# lorasch.net
KiCad netlist of a schematic drawn in EAGLE
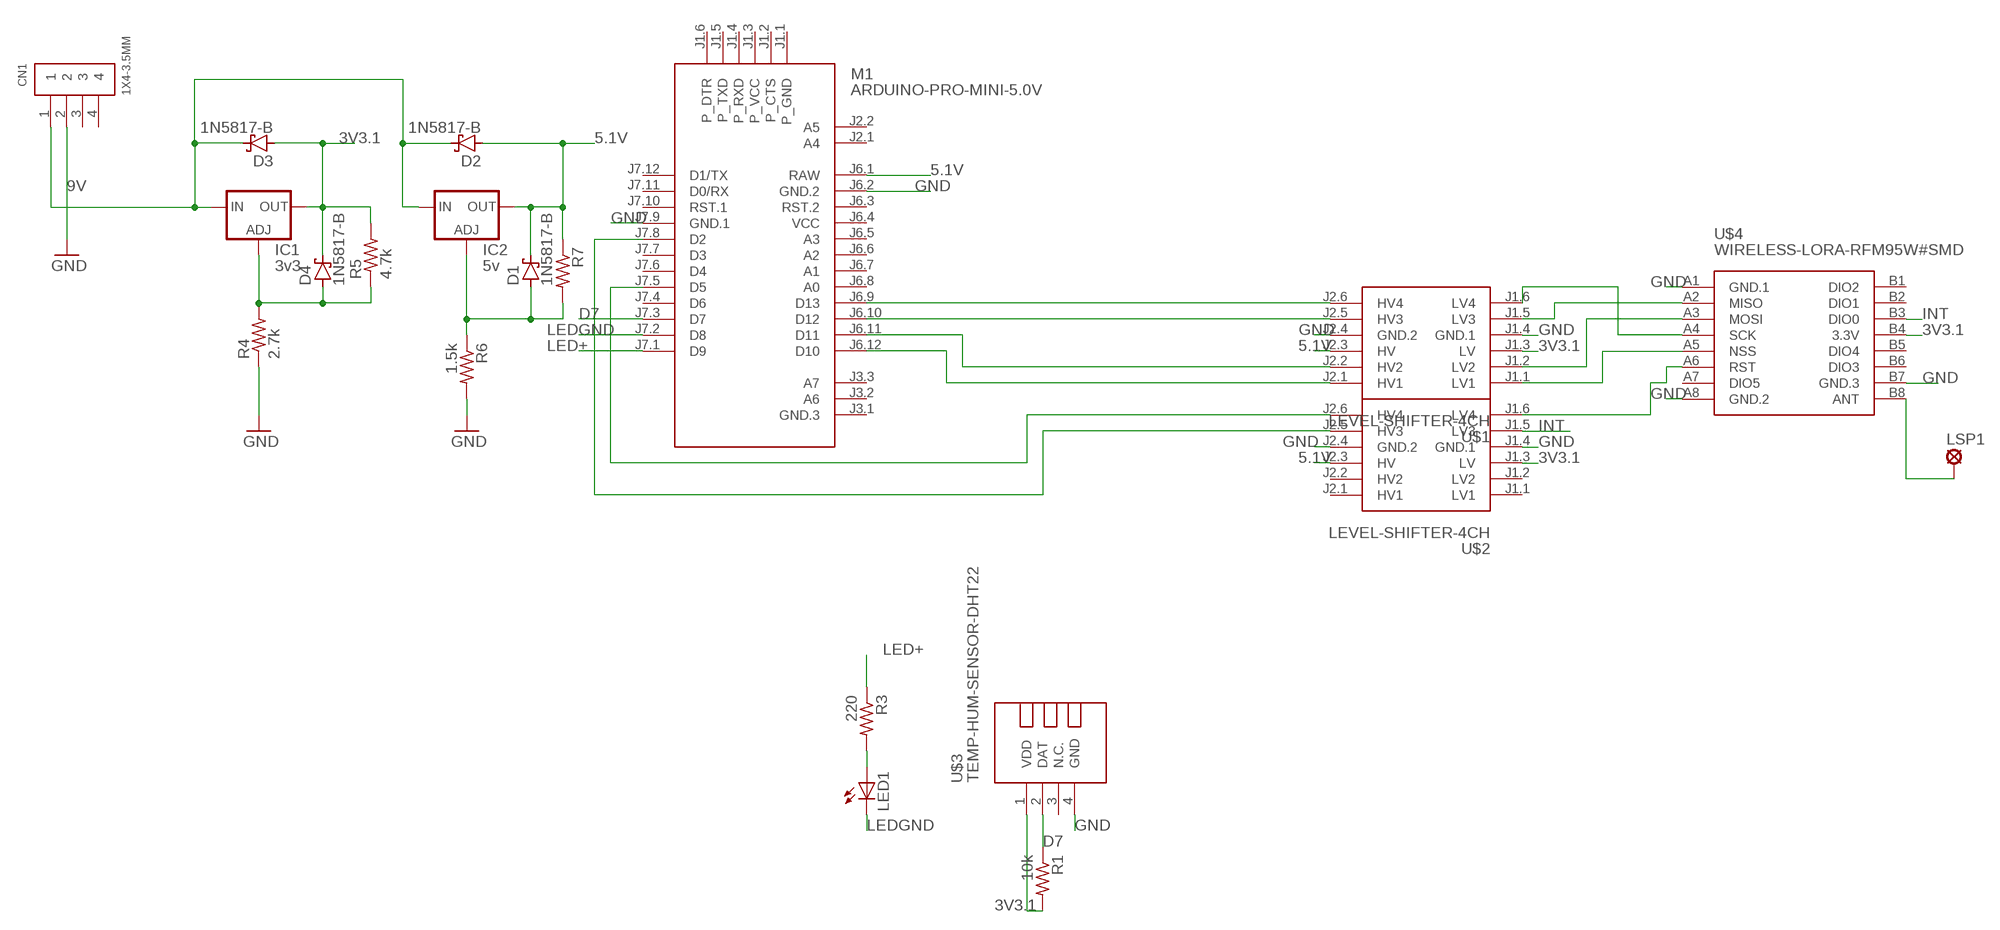
[diagram p0: schematic, sheet 1]

(export (version "E")
  (design (tool "Eeschema 10.0.6"))
  (components
    (comp (ref "CN1")
      (value "1X4-3.5MM")
      (footprint "eagle-import:1X04-3.5MM")
      (libsource (lib "eagle-import") (part "1X4-3.5MM"))
    )
    (comp (ref "D1")
      (value "1N5817-B")
      (footprint "eagle-import:DO41-7.6")
      (libsource (lib "eagle-import") (part "1N5817-B"))
    )
    (comp (ref "D2")
      (value "1N5817-B")
      (footprint "eagle-import:DO41-7.6")
      (libsource (lib "eagle-import") (part "1N5817-B"))
    )
    (comp (ref "D3")
      (value "1N5817-B")
      (footprint "eagle-import:DO41-7.6")
      (libsource (lib "eagle-import") (part "1N5817-B"))
    )
    (comp (ref "D4")
      (value "1N5817-B")
      (footprint "eagle-import:DO41-7.6")
      (libsource (lib "eagle-import") (part "1N5817-B"))
    )
    (comp (ref "IC1")
      (value "3v3")
      (footprint "eagle-import:317TL")
      (libsource (lib "eagle-import") (part "LM317TL"))
    )
    (comp (ref "IC2")
      (value "5v")
      (footprint "eagle-import:317TL")
      (libsource (lib "eagle-import") (part "LM317TL"))
    )
    (comp (ref "LED1")
      (value "LED5MM")
      (footprint "eagle-import:LED5MM")
      (libsource (lib "eagle-import") (part "LED5MM"))
    )
    (comp (ref "LSP1")
      (value "SE14")
      (footprint "eagle-import:SE14")
      (libsource (lib "eagle-import") (part "SE14"))
    )
    (comp (ref "M1")
      (value "ARDUINO-PRO-MINI-5.0V")
      (footprint "eagle-import:ARDUINO-PRO-MINI")
      (libsource (lib "eagle-import") (part "ARDUINO-PRO-MINI-5.0V"))
    )
    (comp (ref "R1")
      (value "10k")
      (footprint "eagle-import:0204_7")
      (libsource (lib "eagle-import") (part "R-US_0204/7"))
    )
    (comp (ref "R3")
      (value "220")
      (footprint "eagle-import:0204_7")
      (libsource (lib "eagle-import") (part "R-US_0204/7"))
    )
    (comp (ref "R4")
      (value "2.7k")
      (footprint "eagle-import:0204_7")
      (libsource (lib "eagle-import") (part "R-US_0204/7"))
    )
    (comp (ref "R5")
      (value "4.7k")
      (footprint "eagle-import:0204_7")
      (libsource (lib "eagle-import") (part "R-US_0204/7"))
    )
    (comp (ref "R6")
      (value "1.5k")
      (footprint "eagle-import:0204_7")
      (libsource (lib "eagle-import") (part "R-US_0204/7"))
    )
    (comp (ref "R7")
      (value "R-US_0204/7")
      (footprint "eagle-import:0204_7")
      (libsource (lib "eagle-import") (part "R-US_0204/7"))
    )
    (comp (ref "U$1")
      (value "LEVEL-SHIFTER-4CH")
      (footprint "eagle-import:LEVEL-SHIFTER-4CH")
      (libsource (lib "eagle-import") (part "LEVEL-SHIFTER-4CH"))
    )
    (comp (ref "U$2")
      (value "LEVEL-SHIFTER-4CH")
      (footprint "eagle-import:LEVEL-SHIFTER-4CH")
      (libsource (lib "eagle-import") (part "LEVEL-SHIFTER-4CH"))
    )
    (comp (ref "U$3")
      (value "TEMP-HUM-SENSOR-DHT22")
      (footprint "eagle-import:TEMP-HUM-SENSOR-DHT22")
      (libsource (lib "eagle-import") (part "TEMP-HUM-SENSOR-DHT22"))
    )
    (comp (ref "U$4")
      (value "WIRELESS-LORA-RFM95W#SMD")
      (footprint "eagle-import:WIRELESS-LORA-RFM95W#SMD")
      (libsource (lib "eagle-import") (part "WIRELESS-LORA-RFM95W#SMD"))
    )
  )
  (nets
    (net (code "1") (name "/3V3.1") (class "Default")
      (node (ref "D3") (pin "A") (pinfunction "A_A") (pintype "passive"))
      (node (ref "D4") (pin "C") (pinfunction "C_C") (pintype "passive"))
      (node (ref "IC1") (pin "2") (pinfunction "OUT_2") (pintype "passive"))
      (node (ref "R1") (pin "2") (pinfunction "2_2") (pintype "passive"))
      (node (ref "R5") (pin "2") (pinfunction "2_2") (pintype "passive"))
      (node (ref "U$1") (pin "J1.3") (pinfunction "LV_J1.3") (pintype "power_in"))
      (node (ref "U$2") (pin "J1.3") (pinfunction "LV_J1.3") (pintype "power_in"))
      (node (ref "U$3") (pin "1") (pinfunction "VDD_1") (pintype "power_in"))
      (node (ref "U$4") (pin "B4") (pinfunction "3.3V_B4") (pintype "power_in"))
    )
    (net (code "2") (name "/5.1V") (class "Default")
      (node (ref "D1") (pin "C") (pinfunction "C_C") (pintype "passive"))
      (node (ref "D2") (pin "A") (pinfunction "A_A") (pintype "passive"))
      (node (ref "IC2") (pin "2") (pinfunction "OUT_2") (pintype "passive"))
      (node (ref "M1") (pin "J6.1") (pinfunction "RAW_J6.1") (pintype "power_in"))
      (node (ref "R7") (pin "1") (pinfunction "1_1") (pintype "passive"))
      (node (ref "U$1") (pin "J2.3") (pinfunction "HV_J2.3") (pintype "power_in"))
      (node (ref "U$2") (pin "J2.3") (pinfunction "HV_J2.3") (pintype "power_in"))
    )
    (net (code "3") (name "/9V") (class "Default")
      (node (ref "CN1") (pin "1") (pinfunction "1_1") (pintype "bidirectional"))
      (node (ref "D2") (pin "C") (pinfunction "C_C") (pintype "passive"))
      (node (ref "D3") (pin "C") (pinfunction "C_C") (pintype "passive"))
      (node (ref "IC1") (pin "3") (pinfunction "IN_3") (pintype "input"))
      (node (ref "IC2") (pin "3") (pinfunction "IN_3") (pintype "input"))
    )
    (net (code "4") (name "/D7") (class "Default")
      (node (ref "M1") (pin "J7.3") (pinfunction "D7_J7.3") (pintype "bidirectional"))
      (node (ref "R1") (pin "1") (pinfunction "1_1") (pintype "passive"))
      (node (ref "U$3") (pin "2") (pinfunction "DAT_2") (pintype "bidirectional"))
    )
    (net (code "5") (name "/INT") (class "Default")
      (node (ref "U$2") (pin "J1.5") (pinfunction "LV3_J1.5") (pintype "bidirectional"))
      (node (ref "U$4") (pin "B3") (pinfunction "DIO0_B3") (pintype "bidirectional"))
    )
    (net (code "6") (name "/LED+") (class "Default")
      (node (ref "M1") (pin "J7.1") (pinfunction "D9_J7.1") (pintype "bidirectional"))
      (node (ref "R3") (pin "1") (pinfunction "1_1") (pintype "passive"))
    )
    (net (code "7") (name "/LEDGND") (class "Default")
      (node (ref "LED1") (pin "K") (pinfunction "C_K") (pintype "passive"))
      (node (ref "M1") (pin "J7.2") (pinfunction "D8_J7.2") (pintype "bidirectional"))
    )
    (net (code "8") (name "/VCC") (class "Default")
      (node (ref "M1") (pin "J6.4") (pinfunction "VCC_J6.4") (pintype "power_in"))
    )
    (net (code "9") (name "GND") (class "Default")
      (node (ref "CN1") (pin "2") (pinfunction "2_2") (pintype "bidirectional"))
      (node (ref "M1") (pin "J6.2") (pinfunction "GND.2_J6.2") (pintype "power_in"))
      (node (ref "M1") (pin "J7.9") (pinfunction "GND.1_J7.9") (pintype "power_in"))
      (node (ref "R4") (pin "1") (pinfunction "1_1") (pintype "passive"))
      (node (ref "R6") (pin "2") (pinfunction "2_2") (pintype "passive"))
      (node (ref "U$1") (pin "J1.4") (pinfunction "GND.1_J1.4") (pintype "power_in"))
      (node (ref "U$1") (pin "J2.4") (pinfunction "GND.2_J2.4") (pintype "power_in"))
      (node (ref "U$2") (pin "J1.4") (pinfunction "GND.1_J1.4") (pintype "power_in"))
      (node (ref "U$2") (pin "J2.4") (pinfunction "GND.2_J2.4") (pintype "power_in"))
      (node (ref "U$3") (pin "4") (pinfunction "GND_4") (pintype "power_in"))
      (node (ref "U$4") (pin "A1") (pinfunction "GND.1_A1") (pintype "power_in"))
      (node (ref "U$4") (pin "A8") (pinfunction "GND.2_A8") (pintype "power_in"))
      (node (ref "U$4") (pin "B7") (pinfunction "GND.3_B7") (pintype "power_in"))
    )
    (net (code "10") (name "Net-(IC1-ADJ)") (class "Default")
      (node (ref "D4") (pin "A") (pinfunction "A_A") (pintype "passive"))
      (node (ref "IC1") (pin "1") (pinfunction "ADJ_1") (pintype "input"))
      (node (ref "R4") (pin "2") (pinfunction "2_2") (pintype "passive"))
      (node (ref "R5") (pin "1") (pinfunction "1_1") (pintype "passive"))
    )
    (net (code "11") (name "Net-(IC2-ADJ)") (class "Default")
      (node (ref "D1") (pin "A") (pinfunction "A_A") (pintype "passive"))
      (node (ref "IC2") (pin "1") (pinfunction "ADJ_1") (pintype "input"))
      (node (ref "R6") (pin "1") (pinfunction "1_1") (pintype "passive"))
      (node (ref "R7") (pin "2") (pinfunction "2_2") (pintype "passive"))
    )
    (net (code "12") (name "Net-(LED1-PadA)") (class "Default")
      (node (ref "LED1") (pin "A") (pinfunction "A_A") (pintype "passive"))
      (node (ref "R3") (pin "2") (pinfunction "2_2") (pintype "passive"))
    )
    (net (code "13") (name "Net-(M1-D2)") (class "Default")
      (node (ref "M1") (pin "J7.8") (pinfunction "D2_J7.8") (pintype "bidirectional"))
      (node (ref "U$2") (pin "J2.5") (pinfunction "HV3_J2.5") (pintype "bidirectional"))
    )
    (net (code "14") (name "Net-(M1-D5)") (class "Default")
      (node (ref "M1") (pin "J7.5") (pinfunction "D5_J7.5") (pintype "bidirectional"))
      (node (ref "U$2") (pin "J2.6") (pinfunction "HV4_J2.6") (pintype "bidirectional"))
    )
    (net (code "15") (name "Net-(M1-D10)") (class "Default")
      (node (ref "M1") (pin "J6.12") (pinfunction "D10_J6.12") (pintype "bidirectional"))
      (node (ref "U$1") (pin "J2.1") (pinfunction "HV1_J2.1") (pintype "bidirectional"))
    )
    (net (code "16") (name "Net-(M1-D11)") (class "Default")
      (node (ref "M1") (pin "J6.11") (pinfunction "D11_J6.11") (pintype "bidirectional"))
      (node (ref "U$1") (pin "J2.2") (pinfunction "HV2_J2.2") (pintype "bidirectional"))
    )
    (net (code "17") (name "Net-(M1-D12)") (class "Default")
      (node (ref "M1") (pin "J6.10") (pinfunction "D12_J6.10") (pintype "bidirectional"))
      (node (ref "U$1") (pin "J2.5") (pinfunction "HV3_J2.5") (pintype "bidirectional"))
    )
    (net (code "18") (name "Net-(M1-D13)") (class "Default")
      (node (ref "M1") (pin "J6.9") (pinfunction "D13_J6.9") (pintype "bidirectional"))
      (node (ref "U$1") (pin "J2.6") (pinfunction "HV4_J2.6") (pintype "bidirectional"))
    )
    (net (code "19") (name "Net-(U$1-LV1)") (class "Default")
      (node (ref "U$1") (pin "J1.1") (pinfunction "LV1_J1.1") (pintype "bidirectional"))
      (node (ref "U$4") (pin "A5") (pinfunction "NSS_A5") (pintype "bidirectional"))
    )
    (net (code "20") (name "Net-(U$1-LV2)") (class "Default")
      (node (ref "U$1") (pin "J1.2") (pinfunction "LV2_J1.2") (pintype "bidirectional"))
      (node (ref "U$4") (pin "A3") (pinfunction "MOSI_A3") (pintype "bidirectional"))
    )
    (net (code "21") (name "Net-(U$1-LV3)") (class "Default")
      (node (ref "U$1") (pin "J1.5") (pinfunction "LV3_J1.5") (pintype "bidirectional"))
      (node (ref "U$4") (pin "A2") (pinfunction "MISO_A2") (pintype "bidirectional"))
    )
    (net (code "22") (name "Net-(U$1-LV4)") (class "Default")
      (node (ref "U$1") (pin "J1.6") (pinfunction "LV4_J1.6") (pintype "bidirectional"))
      (node (ref "U$4") (pin "A4") (pinfunction "SCK_A4") (pintype "bidirectional"))
    )
    (net (code "23") (name "Net-(U$2-LV4)") (class "Default")
      (node (ref "U$2") (pin "J1.6") (pinfunction "LV4_J1.6") (pintype "bidirectional"))
      (node (ref "U$4") (pin "A6") (pinfunction "RST_A6") (pintype "bidirectional"))
    )
    (net (code "24") (name "Net-(U$4-ANT)") (class "Default")
      (node (ref "LSP1") (pin "MP") (pinfunction "MP_MP") (pintype "passive"))
      (node (ref "U$4") (pin "B8") (pinfunction "ANT_B8") (pintype "passive"))
    )
    (net (code "25") (name "unconnected-(CN1-Pad3)") (class "Default")
      (node (ref "CN1") (pin "3") (pinfunction "3_3") (pintype "bidirectional"))
    )
    (net (code "26") (name "unconnected-(CN1-Pad4)") (class "Default")
      (node (ref "CN1") (pin "4") (pinfunction "4_4") (pintype "bidirectional"))
    )
    (net (code "27") (name "unconnected-(M1-A0-PadJ6.8)") (class "Default")
      (node (ref "M1") (pin "J6.8") (pinfunction "A0_J6.8") (pintype "bidirectional"))
    )
    (net (code "28") (name "unconnected-(M1-A1-PadJ6.7)") (class "Default")
      (node (ref "M1") (pin "J6.7") (pinfunction "A1_J6.7") (pintype "bidirectional"))
    )
    (net (code "29") (name "unconnected-(M1-A2-PadJ6.6)") (class "Default")
      (node (ref "M1") (pin "J6.6") (pinfunction "A2_J6.6") (pintype "bidirectional"))
    )
    (net (code "30") (name "unconnected-(M1-A3-PadJ6.5)") (class "Default")
      (node (ref "M1") (pin "J6.5") (pinfunction "A3_J6.5") (pintype "bidirectional"))
    )
    (net (code "31") (name "unconnected-(M1-A4-PadJ2.1)") (class "Default")
      (node (ref "M1") (pin "J2.1") (pinfunction "A4_J2.1") (pintype "bidirectional"))
    )
    (net (code "32") (name "unconnected-(M1-A5-PadJ2.2)") (class "Default")
      (node (ref "M1") (pin "J2.2") (pinfunction "A5_J2.2") (pintype "bidirectional"))
    )
    (net (code "33") (name "unconnected-(M1-A6-PadJ3.2)") (class "Default")
      (node (ref "M1") (pin "J3.2") (pinfunction "A6_J3.2") (pintype "bidirectional"))
    )
    (net (code "34") (name "unconnected-(M1-A7-PadJ3.3)") (class "Default")
      (node (ref "M1") (pin "J3.3") (pinfunction "A7_J3.3") (pintype "bidirectional"))
    )
    (net (code "35") (name "unconnected-(M1-D0{slash}RX-PadJ7.11)") (class "Default")
      (node (ref "M1") (pin "J7.11") (pinfunction "D0/RX_J7.11") (pintype "bidirectional"))
    )
    (net (code "36") (name "unconnected-(M1-D1{slash}TX-PadJ7.12)") (class "Default")
      (node (ref "M1") (pin "J7.12") (pinfunction "D1/TX_J7.12") (pintype "bidirectional"))
    )
    (net (code "37") (name "unconnected-(M1-D3-PadJ7.7)") (class "Default")
      (node (ref "M1") (pin "J7.7") (pinfunction "D3_J7.7") (pintype "bidirectional"))
    )
    (net (code "38") (name "unconnected-(M1-D4-PadJ7.6)") (class "Default")
      (node (ref "M1") (pin "J7.6") (pinfunction "D4_J7.6") (pintype "bidirectional"))
    )
    (net (code "39") (name "unconnected-(M1-D6-PadJ7.4)") (class "Default")
      (node (ref "M1") (pin "J7.4") (pinfunction "D6_J7.4") (pintype "bidirectional"))
    )
    (net (code "40") (name "unconnected-(M1-GND.3-PadJ3.1)") (class "Default")
      (node (ref "M1") (pin "J3.1") (pinfunction "GND.3_J3.1") (pintype "bidirectional"))
    )
    (net (code "41") (name "unconnected-(M1-P_CTS-PadJ1.2)") (class "Default")
      (node (ref "M1") (pin "J1.2") (pinfunction "P_CTS_J1.2") (pintype "bidirectional"))
    )
    (net (code "42") (name "unconnected-(M1-P_DTR-PadJ1.6)") (class "Default")
      (node (ref "M1") (pin "J1.6") (pinfunction "P_DTR_J1.6") (pintype "bidirectional"))
    )
    (net (code "43") (name "unconnected-(M1-P_GND-PadJ1.1)") (class "Default")
      (node (ref "M1") (pin "J1.1") (pinfunction "P_GND_J1.1") (pintype "bidirectional"))
    )
    (net (code "44") (name "unconnected-(M1-P_RXD-PadJ1.4)") (class "Default")
      (node (ref "M1") (pin "J1.4") (pinfunction "P_RXD_J1.4") (pintype "bidirectional"))
    )
    (net (code "45") (name "unconnected-(M1-P_TXD-PadJ1.5)") (class "Default")
      (node (ref "M1") (pin "J1.5") (pinfunction "P_TXD_J1.5") (pintype "bidirectional"))
    )
    (net (code "46") (name "unconnected-(M1-P_VCC-PadJ1.3)") (class "Default")
      (node (ref "M1") (pin "J1.3") (pinfunction "P_VCC_J1.3") (pintype "bidirectional"))
    )
    (net (code "47") (name "unconnected-(M1-RST.1-PadJ7.10)") (class "Default")
      (node (ref "M1") (pin "J7.10") (pinfunction "RST.1_J7.10") (pintype "bidirectional"))
    )
    (net (code "48") (name "unconnected-(M1-RST.2-PadJ6.3)") (class "Default")
      (node (ref "M1") (pin "J6.3") (pinfunction "RST.2_J6.3") (pintype "bidirectional"))
    )
    (net (code "49") (name "unconnected-(U$2-HV1-PadJ2.1)") (class "Default")
      (node (ref "U$2") (pin "J2.1") (pinfunction "HV1_J2.1") (pintype "bidirectional"))
    )
    (net (code "50") (name "unconnected-(U$2-HV2-PadJ2.2)") (class "Default")
      (node (ref "U$2") (pin "J2.2") (pinfunction "HV2_J2.2") (pintype "bidirectional"))
    )
    (net (code "51") (name "unconnected-(U$2-LV1-PadJ1.1)") (class "Default")
      (node (ref "U$2") (pin "J1.1") (pinfunction "LV1_J1.1") (pintype "bidirectional"))
    )
    (net (code "52") (name "unconnected-(U$2-LV2-PadJ1.2)") (class "Default")
      (node (ref "U$2") (pin "J1.2") (pinfunction "LV2_J1.2") (pintype "bidirectional"))
    )
    (net (code "53") (name "unconnected-(U$3-N.C.-Pad3)") (class "Default")
      (node (ref "U$3") (pin "3") (pinfunction "N.C._3") (pintype "passive"))
    )
    (net (code "54") (name "unconnected-(U$4-DIO1-PadB2)") (class "Default")
      (node (ref "U$4") (pin "B2") (pinfunction "DIO1_B2") (pintype "bidirectional"))
    )
    (net (code "55") (name "unconnected-(U$4-DIO2-PadB1)") (class "Default")
      (node (ref "U$4") (pin "B1") (pinfunction "DIO2_B1") (pintype "bidirectional"))
    )
    (net (code "56") (name "unconnected-(U$4-DIO3-PadB6)") (class "Default")
      (node (ref "U$4") (pin "B6") (pinfunction "DIO3_B6") (pintype "bidirectional"))
    )
    (net (code "57") (name "unconnected-(U$4-DIO4-PadB5)") (class "Default")
      (node (ref "U$4") (pin "B5") (pinfunction "DIO4_B5") (pintype "bidirectional"))
    )
    (net (code "58") (name "unconnected-(U$4-DIO5-PadA7)") (class "Default")
      (node (ref "U$4") (pin "A7") (pinfunction "DIO5_A7") (pintype "bidirectional"))
    )
  )
)
